# Top_Level.net
KiCad netlist of a schematic drawn in Altium Designer
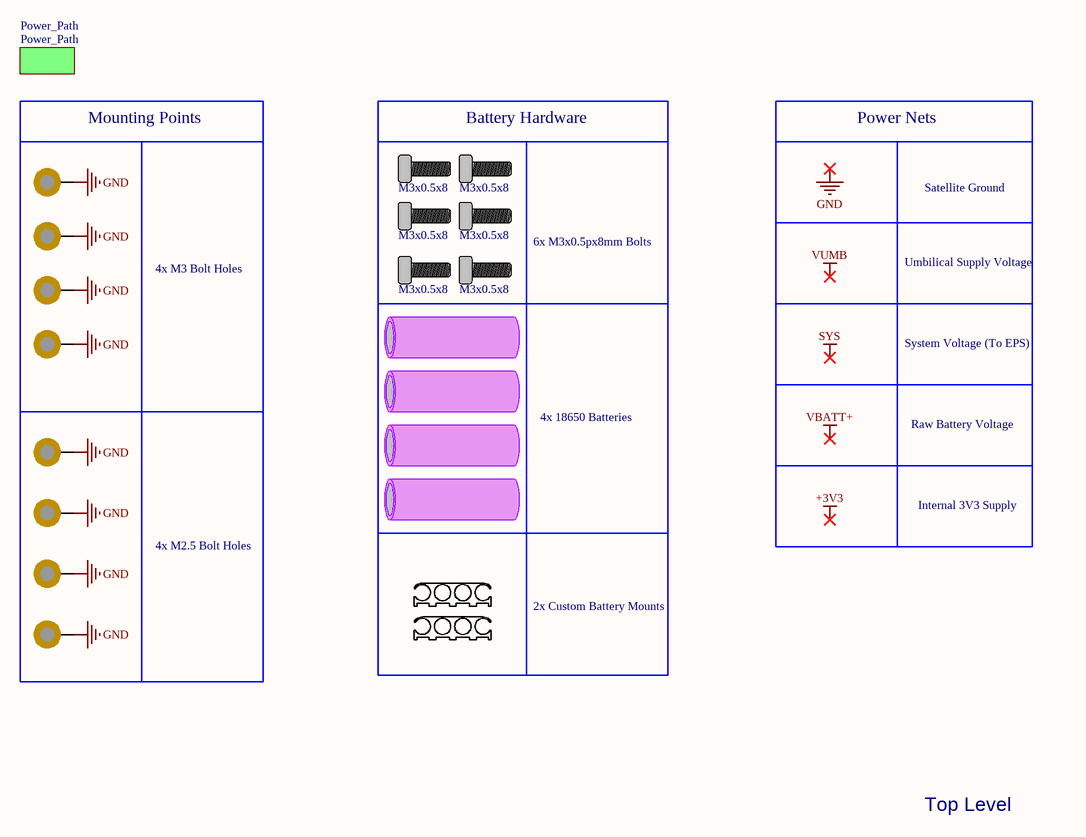
[diagram p0: Top_Level.SchDoc]

(export (version "E")
  (design (tool "Eeschema 10.0.6"))
  (components
    (comp (ref "BAT1")
      (value "INR18650-35E")
      (description "Samsung 3500mAh 18650 Li-Ion battery")
      (fields (field (name "DISTRIBUTOR PART NUMBER") "SB2632"))
      (libsource (lib "Ahristi_Library") (part "INR18650-35E"))
    )
    (comp (ref "BAT2")
      (value "INR18650-35E")
      (description "Samsung 3500mAh 18650 Li-Ion battery")
      (fields (field (name "DISTRIBUTOR PART NUMBER") "SB2632"))
      (libsource (lib "Ahristi_Library") (part "INR18650-35E"))
    )
    (comp (ref "BAT3")
      (value "INR18650-35E")
      (description "Samsung 3500mAh 18650 Li-Ion battery")
      (fields (field (name "DISTRIBUTOR PART NUMBER") "SB2632"))
      (libsource (lib "Ahristi_Library") (part "INR18650-35E"))
    )
    (comp (ref "BAT4")
      (value "INR18650-35E")
      (description "Samsung 3500mAh 18650 Li-Ion battery")
      (fields (field (name "DISTRIBUTOR PART NUMBER") "SB2632"))
      (libsource (lib "Ahristi_Library") (part "INR18650-35E"))
    )
    (comp (ref "MECH1")
      (value "M3 Mounting Hole")
      (footprint "M3 Mounting Hole")
      (libsource (lib "Ahristi_Library") (part "M3 Mounting Hole"))
    )
    (comp (ref "MECH2")
      (value "M3 Mounting Hole")
      (footprint "M3 Mounting Hole")
      (libsource (lib "Ahristi_Library") (part "M3 Mounting Hole"))
    )
    (comp (ref "MECH3")
      (value "M3 Mounting Hole")
      (footprint "M3 Mounting Hole")
      (libsource (lib "Ahristi_Library") (part "M3 Mounting Hole"))
    )
    (comp (ref "MECH4")
      (value "M3 Mounting Hole")
      (footprint "M3 Mounting Hole")
      (libsource (lib "Ahristi_Library") (part "M3 Mounting Hole"))
    )
    (comp (ref "MECH5")
      (value "M3x0.5x8")
      (footprint "M3 x 0.50p x 8mm Bolt")
      (fields (field (name "PART NUMBER") "M3 x 0.50p x 8mm"))
      (libsource (lib "Ahristi_Library") (part "M3x0.5px8mm Bolt"))
    )
    (comp (ref "MECH6")
      (value "M3x0.5x8")
      (footprint "M3 x 0.50p x 8mm Bolt")
      (fields (field (name "PART NUMBER") "M3 x 0.50p x 8mm"))
      (libsource (lib "Ahristi_Library") (part "M3x0.5px8mm Bolt"))
    )
    (comp (ref "MECH7")
      (value "M3x0.5x8")
      (footprint "M3 x 0.50p x 8mm Bolt")
      (fields (field (name "PART NUMBER") "M3 x 0.50p x 8mm"))
      (libsource (lib "Ahristi_Library") (part "M3x0.5px8mm Bolt"))
    )
    (comp (ref "MECH8")
      (value "M3x0.5x8")
      (footprint "M3 x 0.50p x 8mm Bolt")
      (fields (field (name "PART NUMBER") "M3 x 0.50p x 8mm"))
      (libsource (lib "Ahristi_Library") (part "M3x0.5px8mm Bolt"))
    )
    (comp (ref "MECH9")
      (value "M3x0.5x8")
      (footprint "M3 x 0.50p x 8mm Bolt")
      (fields (field (name "PART NUMBER") "M3 x 0.50p x 8mm"))
      (libsource (lib "Ahristi_Library") (part "M3x0.5px8mm Bolt"))
    )
    (comp (ref "MECH10")
      (value "M3x0.5x8")
      (footprint "M3 x 0.50p x 8mm Bolt")
      (fields (field (name "PART NUMBER") "M3 x 0.50p x 8mm"))
      (libsource (lib "Ahristi_Library") (part "M3x0.5px8mm Bolt"))
    )
    (comp (ref "MECH11")
      (value "M2.5 Mounting Hole")
      (footprint "M2.5 Mounting Hole")
      (libsource (lib "Ahristi_Library") (part "M2.5 Mounting Hole"))
    )
    (comp (ref "MECH12")
      (value "M2.5 Mounting Hole")
      (footprint "M2.5 Mounting Hole")
      (libsource (lib "Ahristi_Library") (part "M2.5 Mounting Hole"))
    )
    (comp (ref "MECH13")
      (value "M2.5 Mounting Hole")
      (footprint "M2.5 Mounting Hole")
      (libsource (lib "Ahristi_Library") (part "M2.5 Mounting Hole"))
    )
    (comp (ref "MECH14")
      (value "M2.5 Mounting Hole")
      (footprint "M2.5 Mounting Hole")
      (libsource (lib "Ahristi_Library") (part "M2.5 Mounting Hole"))
    )
  )
  (nets
    (net (code "2") (name "GND") (class "Default")
      (node (ref "MECH1") (pin "1") (pinfunction "1_1") (pintype "passive"))
      (node (ref "MECH11") (pin "1") (pinfunction "1_1") (pintype "passive"))
      (node (ref "MECH12") (pin "1") (pinfunction "1_1") (pintype "passive"))
      (node (ref "MECH13") (pin "1") (pinfunction "1_1") (pintype "passive"))
      (node (ref "MECH14") (pin "1") (pinfunction "1_1") (pintype "passive"))
      (node (ref "MECH2") (pin "1") (pinfunction "1_1") (pintype "passive"))
      (node (ref "MECH3") (pin "1") (pinfunction "1_1") (pintype "passive"))
      (node (ref "MECH4") (pin "1") (pinfunction "1_1") (pintype "passive"))
    )
  )
)
